# SpectroSlave.net
KiCad netlist of a schematic drawn in EAGLE
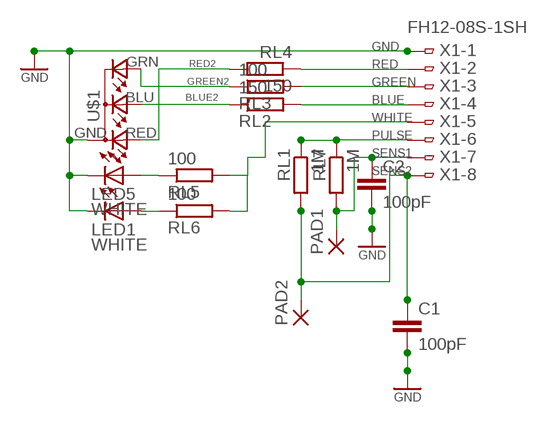
[diagram p0: schematic, sheet 1]

(export (version "E")
  (design (tool "Eeschema 10.0.6"))
  (components
    (comp (ref "C1")
      (value "100pF")
      (footprint "eagle-import:C0805")
      (libsource (lib "eagle-import") (part "C-EUC0805"))
    )
    (comp (ref "C2")
      (value "100pF")
      (footprint "eagle-import:C0805")
      (libsource (lib "eagle-import") (part "C-EUC0805"))
    )
    (comp (ref "LED1")
      (value "WHITE")
      (footprint "eagle-import:LED3MM")
      (libsource (lib "eagle-import") (part "LED3MM"))
    )
    (comp (ref "LED5")
      (value "WHITE")
      (footprint "eagle-import:LED3MM")
      (libsource (lib "eagle-import") (part "LED3MM"))
    )
    (comp (ref "PAD1")
      (value "SMD5")
      (footprint "eagle-import:SMD2,54-5,08")
      (libsource (lib "eagle-import") (part "SMD5"))
    )
    (comp (ref "PAD2")
      (value "SMD5")
      (footprint "eagle-import:SMD2,54-5,08")
      (libsource (lib "eagle-import") (part "SMD5"))
    )
    (comp (ref "RL1")
      (value "1M")
      (footprint "eagle-import:R0805")
      (libsource (lib "eagle-import") (part "R-EU_R0805"))
    )
    (comp (ref "RL2")
      (value "150")
      (footprint "eagle-import:R0805")
      (libsource (lib "eagle-import") (part "R-EU_R0805"))
    )
    (comp (ref "RL3")
      (value "100")
      (footprint "eagle-import:R0805")
      (libsource (lib "eagle-import") (part "R-EU_R0805"))
    )
    (comp (ref "RL4")
      (value "150")
      (footprint "eagle-import:R0805")
      (libsource (lib "eagle-import") (part "R-EU_R0805"))
    )
    (comp (ref "RL5")
      (value "100")
      (footprint "eagle-import:R0805")
      (libsource (lib "eagle-import") (part "R-EU_R0805"))
    )
    (comp (ref "RL6")
      (value "100")
      (footprint "eagle-import:R0805")
      (libsource (lib "eagle-import") (part "R-EU_R0805"))
    )
    (comp (ref "RL7")
      (value "1M")
      (footprint "eagle-import:R0805")
      (libsource (lib "eagle-import") (part "R-EU_R0805"))
    )
    (comp (ref "U$1")
      (value "RGB-COMMON-CATHODE")
      (footprint "eagle-import:LED-TRICOLOR-THROUGHHOLE")
      (libsource (lib "eagle-import") (part "RGB-COMMON-CATHODE"))
    )
    (comp (ref "X1")
      (value "FH12-08S-1SH")
      (footprint "eagle-import:FH12-08S-1SH")
      (libsource (lib "eagle-import") (part "FH12-08S-1SH"))
    )
  )
  (nets
    (net (code "1") (name "/BLUE") (class "Default")
      (node (ref "RL2") (pin "2") (pinfunction "2_2") (pintype "passive"))
      (node (ref "X1") (pin "4") (pinfunction "1_4") (pintype "passive"))
    )
    (net (code "2") (name "/BLUE2") (class "Default")
      (node (ref "RL2") (pin "1") (pinfunction "1_1") (pintype "passive"))
      (node (ref "U$1") (pin "BLU") (pinfunction "CBLUE_BLU") (pintype "passive"))
    )
    (net (code "3") (name "/GREEN") (class "Default")
      (node (ref "RL3") (pin "2") (pinfunction "2_2") (pintype "passive"))
      (node (ref "X1") (pin "3") (pinfunction "1_3") (pintype "passive"))
    )
    (net (code "4") (name "/GREEN2") (class "Default")
      (node (ref "RL3") (pin "1") (pinfunction "1_1") (pintype "passive"))
      (node (ref "U$1") (pin "GRN") (pinfunction "CGREEN_GRN") (pintype "passive"))
    )
    (net (code "5") (name "/PULSE") (class "Default")
      (node (ref "RL1") (pin "1") (pinfunction "1_1") (pintype "passive"))
      (node (ref "RL7") (pin "1") (pinfunction "1_1") (pintype "passive"))
      (node (ref "X1") (pin "6") (pinfunction "1_6") (pintype "passive"))
    )
    (net (code "6") (name "/RED") (class "Default")
      (node (ref "RL4") (pin "1") (pinfunction "1_1") (pintype "passive"))
      (node (ref "X1") (pin "2") (pinfunction "1_2") (pintype "passive"))
    )
    (net (code "7") (name "/RED2") (class "Default")
      (node (ref "RL4") (pin "2") (pinfunction "2_2") (pintype "passive"))
      (node (ref "U$1") (pin "RED") (pinfunction "CRED_RED") (pintype "passive"))
    )
    (net (code "8") (name "/SENS1") (class "Default")
      (node (ref "C2") (pin "1") (pinfunction "1_1") (pintype "passive"))
      (node (ref "PAD1") (pin "1") (pinfunction "P_1") (pintype "passive"))
      (node (ref "RL7") (pin "2") (pinfunction "2_2") (pintype "passive"))
      (node (ref "X1") (pin "7") (pinfunction "1_7") (pintype "passive"))
    )
    (net (code "9") (name "/SENS2") (class "Default")
      (node (ref "C1") (pin "1") (pinfunction "1_1") (pintype "passive"))
      (node (ref "PAD2") (pin "1") (pinfunction "P_1") (pintype "passive"))
      (node (ref "RL1") (pin "2") (pinfunction "2_2") (pintype "passive"))
      (node (ref "X1") (pin "8") (pinfunction "1_8") (pintype "passive"))
    )
    (net (code "10") (name "/WHITE") (class "Default")
      (node (ref "RL5") (pin "2") (pinfunction "2_2") (pintype "passive"))
      (node (ref "RL6") (pin "2") (pinfunction "2_2") (pintype "passive"))
      (node (ref "X1") (pin "5") (pinfunction "1_5") (pintype "passive"))
    )
    (net (code "11") (name "GND") (class "Default")
      (node (ref "C1") (pin "2") (pinfunction "2_2") (pintype "passive"))
      (node (ref "C2") (pin "2") (pinfunction "2_2") (pintype "passive"))
      (node (ref "LED1") (pin "K") (pinfunction "C_K") (pintype "passive"))
      (node (ref "LED5") (pin "K") (pinfunction "C_K") (pintype "passive"))
      (node (ref "U$1") (pin "GND") (pinfunction "A2_GND") (pintype "passive"))
      (node (ref "X1") (pin "1") (pinfunction "1_1") (pintype "passive"))
    )
    (net (code "12") (name "Net-(LED1-PadA)") (class "Default")
      (node (ref "LED1") (pin "A") (pinfunction "A_A") (pintype "passive"))
      (node (ref "RL6") (pin "1") (pinfunction "1_1") (pintype "passive"))
    )
    (net (code "13") (name "Net-(LED5-PadA)") (class "Default")
      (node (ref "LED5") (pin "A") (pinfunction "A_A") (pintype "passive"))
      (node (ref "RL5") (pin "1") (pinfunction "1_1") (pintype "passive"))
    )
  )
)
